# Serial.net
KiCad netlist of a schematic drawn in Altium Designer
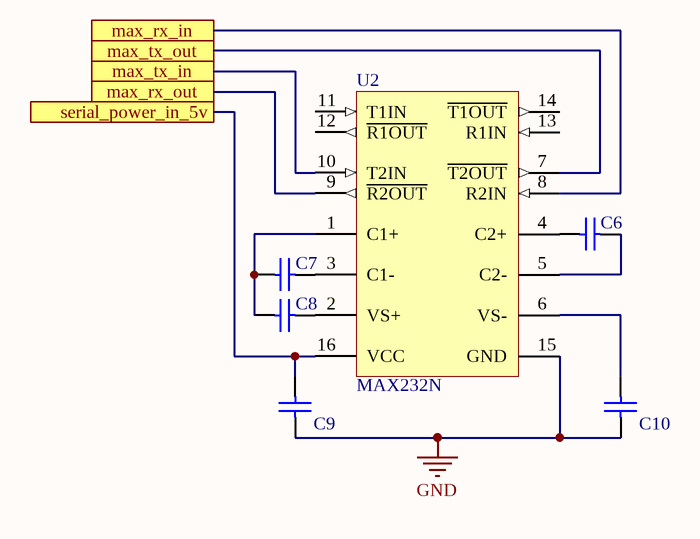
[diagram p0: Serial.SchDoc]

(export (version "E")
  (design (tool "Eeschema 10.0.6"))
  (components
    (comp (ref "C6")
      (value "CAP_1_21_4")
      (footprint "0402")
      (description "1uF 10% 10V")
      (fields (field (name "TOLERANCE") "10%") (field (name "VOLTAGE") "10V"))
      (libsource (lib "CPHComponentSource") (part "CAP_1_21_4"))
    )
    (comp (ref "C7")
      (value "CAP_1_21_4")
      (footprint "0402")
      (description "1uF 10% 10V")
      (fields (field (name "TOLERANCE") "10%") (field (name "VOLTAGE") "10V"))
      (libsource (lib "CPHComponentSource") (part "CAP_1_21_4"))
    )
    (comp (ref "C8")
      (value "CAP_1_21_4")
      (footprint "0402")
      (description "1uF 10% 10V")
      (fields (field (name "TOLERANCE") "10%") (field (name "VOLTAGE") "10V"))
      (libsource (lib "CPHComponentSource") (part "CAP_1_21_4"))
    )
    (comp (ref "C9")
      (value "CAP_1_21_4")
      (footprint "0402")
      (description "1uF 10% 10V")
      (fields (field (name "TOLERANCE") "10%") (field (name "VOLTAGE") "10V"))
      (libsource (lib "CPHComponentSource") (part "CAP_1_21_4"))
    )
    (comp (ref "C10")
      (value "CAP_1_21_4")
      (footprint "0402")
      (description "1uF 10% 10V")
      (fields (field (name "TOLERANCE") "10%") (field (name "VOLTAGE") "10V"))
      (libsource (lib "CPHComponentSource") (part "CAP_1_21_4"))
    )
    (comp (ref "U2")
      (value "MAX232N")
      (footprint "N0016A")
      (description "Dual EIA-232 Driver / Receiver, 0 to 70 degC, 16-Pin PDIP (N), Pb-Free (RoHS)")
      (libsource (lib "Altium Content Vault") (part "TI-MAX232-PDIP_N-16"))
    )
  )
  (nets
    (net (code "1") (name "/max_rx_in") (class "Default")
      (node (ref "U2") (pin "8") (pinfunction "R2IN_8") (pintype "input"))
    )
    (net (code "2") (name "/max_rx_out") (class "Default")
      (node (ref "U2") (pin "9") (pinfunction "~{R2OUT}_9") (pintype "output"))
    )
    (net (code "3") (name "/max_tx_in") (class "Default")
      (node (ref "U2") (pin "10") (pinfunction "T2IN_10") (pintype "input"))
    )
    (net (code "4") (name "/max_tx_out") (class "Default")
      (node (ref "U2") (pin "7") (pinfunction "~{T2OUT}_7") (pintype "output"))
    )
    (net (code "5") (name "/serial_power_in_5v") (class "Default")
      (node (ref "C9") (pin "2") (pinfunction "2_2") (pintype "passive"))
      (node (ref "U2") (pin "16") (pinfunction "VCC_16") (pintype "power_in"))
    )
    (net (code "6") (name "GND") (class "Default")
      (node (ref "C10") (pin "1") (pinfunction "1_1") (pintype "passive"))
      (node (ref "C9") (pin "1") (pinfunction "1_1") (pintype "passive"))
      (node (ref "U2") (pin "15") (pinfunction "GND_15") (pintype "power_in"))
    )
    (net (code "7") (name "Net-(U2-C1+)") (class "Default")
      (node (ref "C7") (pin "1") (pinfunction "1_1") (pintype "passive"))
      (node (ref "C8") (pin "1") (pinfunction "1_1") (pintype "passive"))
      (node (ref "U2") (pin "1") (pinfunction "C1+_1") (pintype "passive"))
    )
    (net (code "8") (name "Net-(U2-C1-)") (class "Default")
      (node (ref "C7") (pin "2") (pinfunction "2_2") (pintype "passive"))
      (node (ref "U2") (pin "3") (pinfunction "C1-_3") (pintype "passive"))
    )
    (net (code "9") (name "Net-(U2-C2+)") (class "Default")
      (node (ref "C6") (pin "1") (pinfunction "1_1") (pintype "passive"))
      (node (ref "U2") (pin "4") (pinfunction "C2+_4") (pintype "passive"))
    )
    (net (code "10") (name "Net-(U2-C2-)") (class "Default")
      (node (ref "C6") (pin "2") (pinfunction "2_2") (pintype "passive"))
      (node (ref "U2") (pin "5") (pinfunction "C2-_5") (pintype "passive"))
    )
    (net (code "11") (name "Net-(U2-VS+)") (class "Default")
      (node (ref "C8") (pin "2") (pinfunction "2_2") (pintype "passive"))
      (node (ref "U2") (pin "2") (pinfunction "VS+_2") (pintype "power_in"))
    )
    (net (code "12") (name "Net-(U2-VS-)") (class "Default")
      (node (ref "C10") (pin "2") (pinfunction "2_2") (pintype "passive"))
      (node (ref "U2") (pin "6") (pinfunction "VS-_6") (pintype "power_in"))
    )
    (net (code "13") (name "unconnected-(U2-R1IN-Pad13)") (class "Default")
      (node (ref "U2") (pin "13") (pinfunction "R1IN_13") (pintype "input"))
    )
    (net (code "14") (name "unconnected-(U2-T1IN-Pad11)") (class "Default")
      (node (ref "U2") (pin "11") (pinfunction "T1IN_11") (pintype "input"))
    )
    (net (code "15") (name "unconnected-(U2-~{R1OUT}-Pad12)") (class "Default")
      (node (ref "U2") (pin "12") (pinfunction "~{R1OUT}_12") (pintype "output"))
    )
    (net (code "16") (name "unconnected-(U2-~{T1OUT}-Pad14)") (class "Default")
      (node (ref "U2") (pin "14") (pinfunction "~{T1OUT}_14") (pintype "output"))
    )
  )
)
